# LED_Matrix.net
KiCad netlist of a schematic drawn in Altium Designer
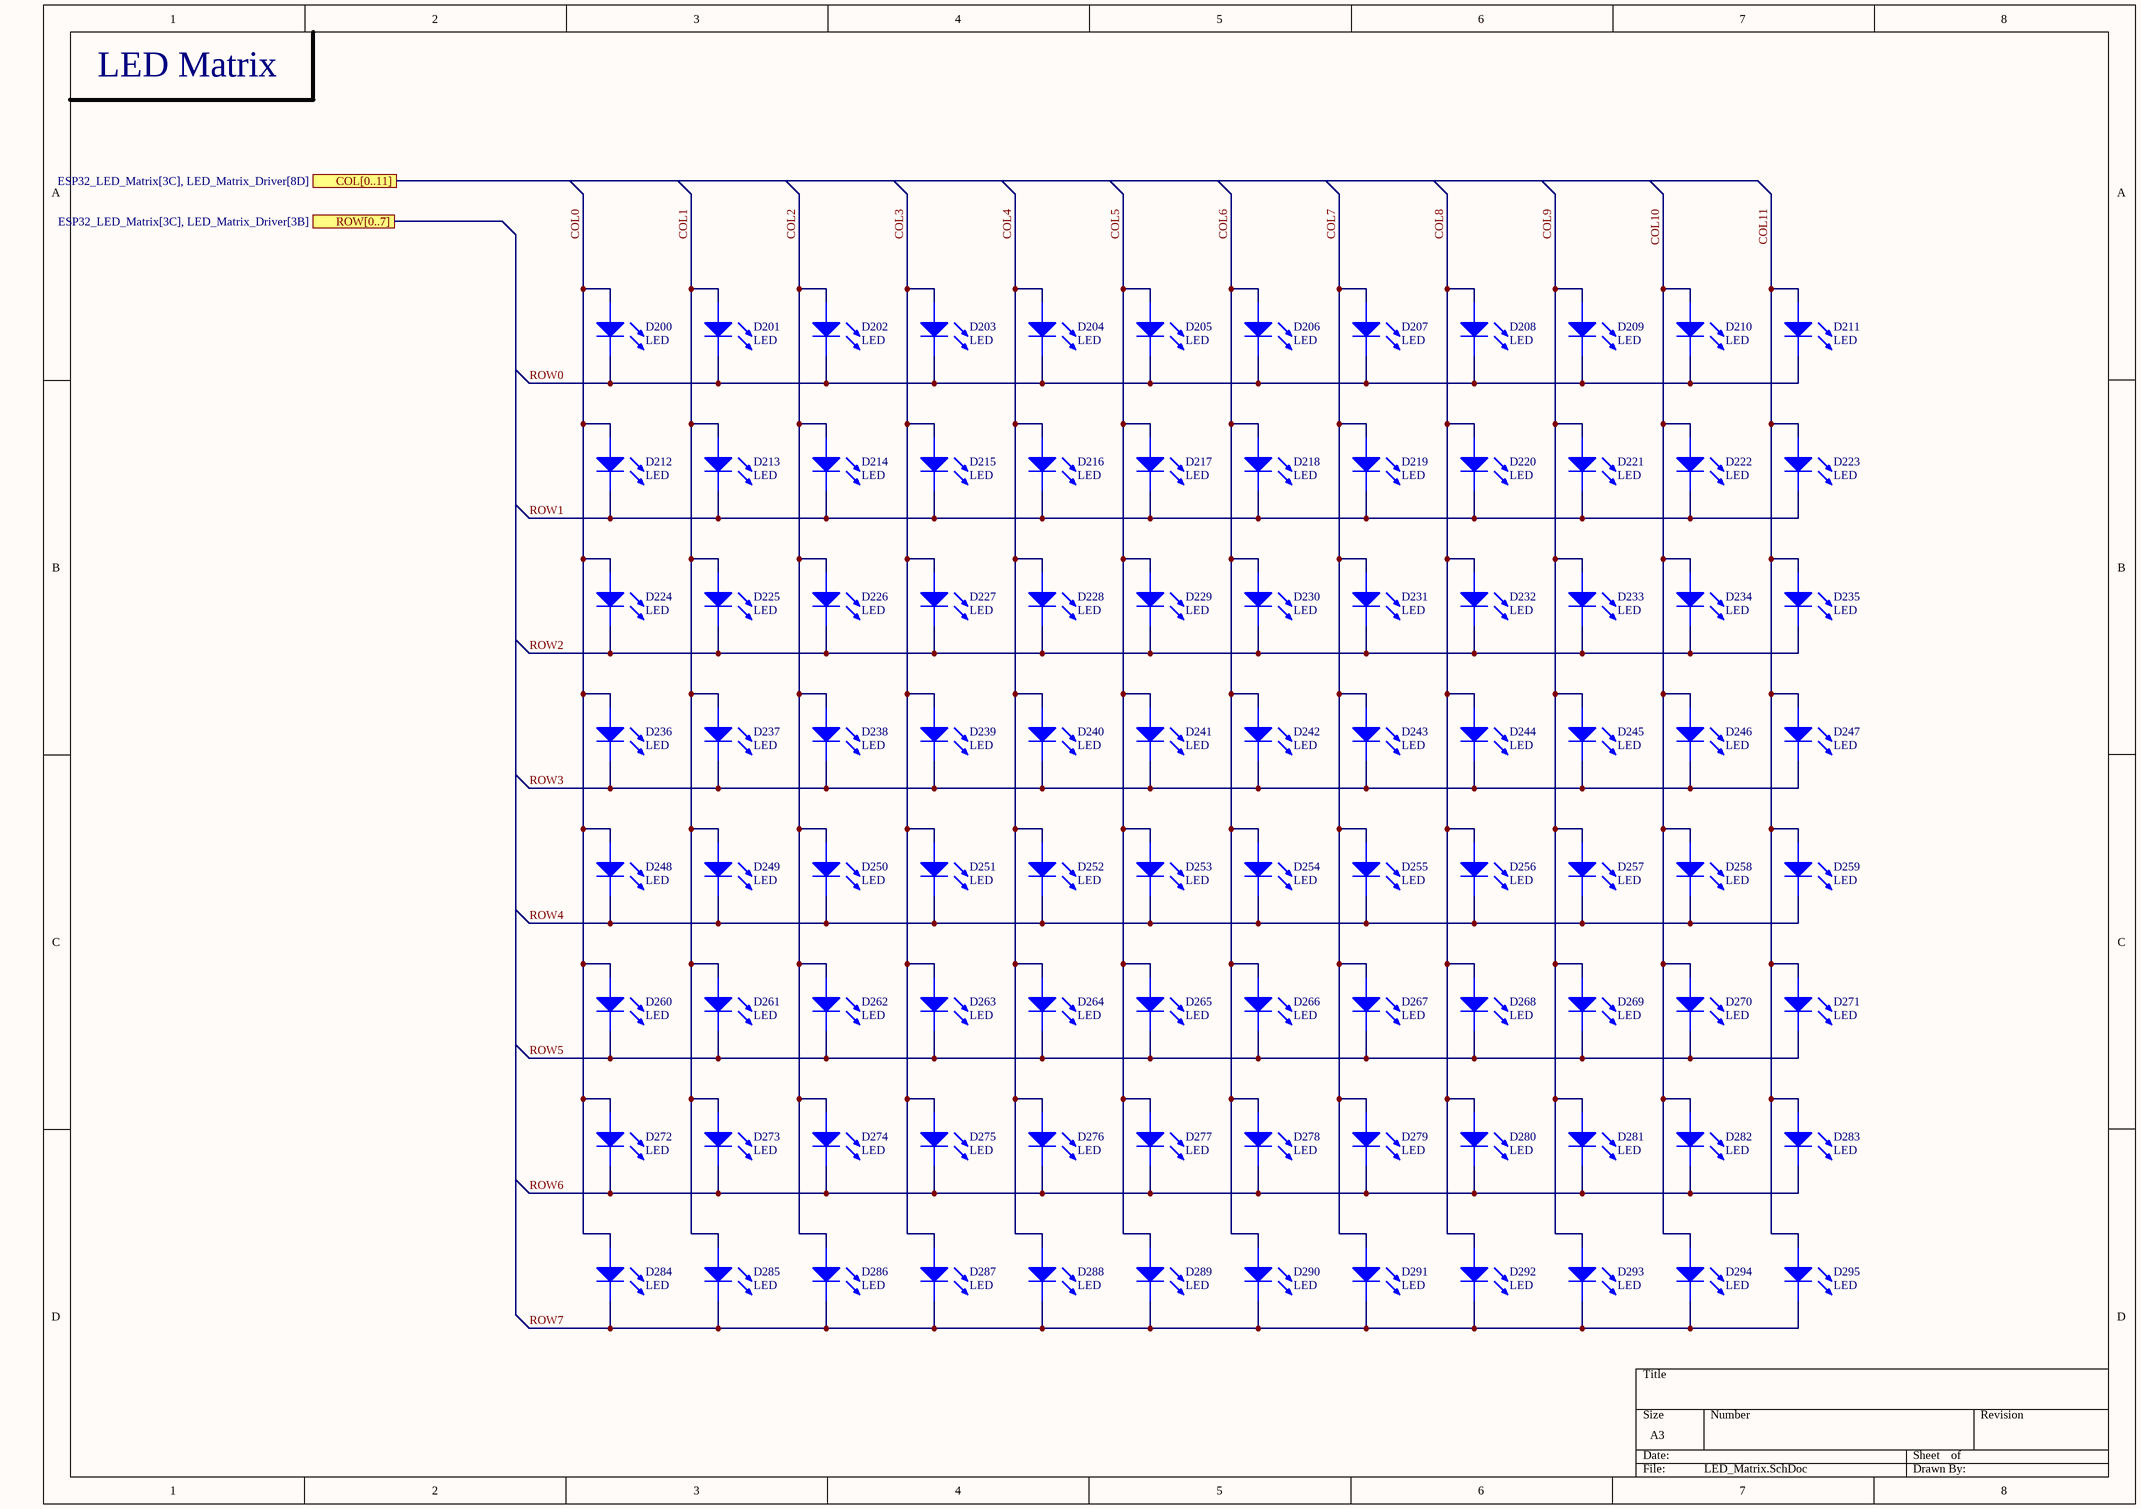
[diagram p0: LED_Matrix.SchDoc]

(export (version "E")
  (design (tool "Eeschema 10.0.6"))
  (components
    (comp (ref "D200")
      (value "LED")
      (footprint "IEEE_Workshop_Footprints:LEDM2012X80N")
      (description "General Purpose LED")
      (libsource (lib "TD") (part "LED"))
    )
    (comp (ref "D201")
      (value "LED")
      (footprint "IEEE_Workshop_Footprints:LEDM2012X80N")
      (description "General Purpose LED")
      (libsource (lib "TD") (part "LED"))
    )
    (comp (ref "D202")
      (value "LED")
      (footprint "IEEE_Workshop_Footprints:LEDM2012X80N")
      (description "General Purpose LED")
      (libsource (lib "TD") (part "LED"))
    )
    (comp (ref "D203")
      (value "LED")
      (footprint "IEEE_Workshop_Footprints:LEDM2012X80N")
      (description "General Purpose LED")
      (libsource (lib "TD") (part "LED"))
    )
    (comp (ref "D204")
      (value "LED")
      (footprint "IEEE_Workshop_Footprints:LEDM2012X80N")
      (description "General Purpose LED")
      (libsource (lib "TD") (part "LED"))
    )
    (comp (ref "D205")
      (value "LED")
      (footprint "IEEE_Workshop_Footprints:LEDM2012X80N")
      (description "General Purpose LED")
      (libsource (lib "TD") (part "LED"))
    )
    (comp (ref "D206")
      (value "LED")
      (footprint "IEEE_Workshop_Footprints:LEDM2012X80N")
      (description "General Purpose LED")
      (libsource (lib "TD") (part "LED"))
    )
    (comp (ref "D207")
      (value "LED")
      (footprint "IEEE_Workshop_Footprints:LEDM2012X80N")
      (description "General Purpose LED")
      (libsource (lib "TD") (part "LED"))
    )
    (comp (ref "D208")
      (value "LED")
      (footprint "IEEE_Workshop_Footprints:LEDM2012X80N")
      (description "General Purpose LED")
      (libsource (lib "TD") (part "LED"))
    )
    (comp (ref "D209")
      (value "LED")
      (footprint "IEEE_Workshop_Footprints:LEDM2012X80N")
      (description "General Purpose LED")
      (libsource (lib "TD") (part "LED"))
    )
    (comp (ref "D210")
      (value "LED")
      (footprint "IEEE_Workshop_Footprints:LEDM2012X80N")
      (description "General Purpose LED")
      (libsource (lib "TD") (part "LED"))
    )
    (comp (ref "D211")
      (value "LED")
      (footprint "IEEE_Workshop_Footprints:LEDM2012X80N")
      (description "General Purpose LED")
      (libsource (lib "TD") (part "LED"))
    )
    (comp (ref "D212")
      (value "LED")
      (footprint "IEEE_Workshop_Footprints:LEDM2012X80N")
      (description "General Purpose LED")
      (libsource (lib "TD") (part "LED"))
    )
    (comp (ref "D213")
      (value "LED")
      (footprint "IEEE_Workshop_Footprints:LEDM2012X80N")
      (description "General Purpose LED")
      (libsource (lib "TD") (part "LED"))
    )
    (comp (ref "D214")
      (value "LED")
      (footprint "IEEE_Workshop_Footprints:LEDM2012X80N")
      (description "General Purpose LED")
      (libsource (lib "TD") (part "LED"))
    )
    (comp (ref "D215")
      (value "LED")
      (footprint "IEEE_Workshop_Footprints:LEDM2012X80N")
      (description "General Purpose LED")
      (libsource (lib "TD") (part "LED"))
    )
    (comp (ref "D216")
      (value "LED")
      (footprint "IEEE_Workshop_Footprints:LEDM2012X80N")
      (description "General Purpose LED")
      (libsource (lib "TD") (part "LED"))
    )
    (comp (ref "D217")
      (value "LED")
      (footprint "IEEE_Workshop_Footprints:LEDM2012X80N")
      (description "General Purpose LED")
      (libsource (lib "TD") (part "LED"))
    )
    (comp (ref "D218")
      (value "LED")
      (footprint "IEEE_Workshop_Footprints:LEDM2012X80N")
      (description "General Purpose LED")
      (libsource (lib "TD") (part "LED"))
    )
    (comp (ref "D219")
      (value "LED")
      (footprint "IEEE_Workshop_Footprints:LEDM2012X80N")
      (description "General Purpose LED")
      (libsource (lib "TD") (part "LED"))
    )
    (comp (ref "D220")
      (value "LED")
      (footprint "IEEE_Workshop_Footprints:LEDM2012X80N")
      (description "General Purpose LED")
      (libsource (lib "TD") (part "LED"))
    )
    (comp (ref "D221")
      (value "LED")
      (footprint "IEEE_Workshop_Footprints:LEDM2012X80N")
      (description "General Purpose LED")
      (libsource (lib "TD") (part "LED"))
    )
    (comp (ref "D222")
      (value "LED")
      (footprint "IEEE_Workshop_Footprints:LEDM2012X80N")
      (description "General Purpose LED")
      (libsource (lib "TD") (part "LED"))
    )
    (comp (ref "D223")
      (value "LED")
      (footprint "IEEE_Workshop_Footprints:LEDM2012X80N")
      (description "General Purpose LED")
      (libsource (lib "TD") (part "LED"))
    )
    (comp (ref "D224")
      (value "LED")
      (footprint "IEEE_Workshop_Footprints:LEDM2012X80N")
      (description "General Purpose LED")
      (libsource (lib "TD") (part "LED"))
    )
    (comp (ref "D225")
      (value "LED")
      (footprint "IEEE_Workshop_Footprints:LEDM2012X80N")
      (description "General Purpose LED")
      (libsource (lib "TD") (part "LED"))
    )
    (comp (ref "D226")
      (value "LED")
      (footprint "IEEE_Workshop_Footprints:LEDM2012X80N")
      (description "General Purpose LED")
      (libsource (lib "TD") (part "LED"))
    )
    (comp (ref "D227")
      (value "LED")
      (footprint "IEEE_Workshop_Footprints:LEDM2012X80N")
      (description "General Purpose LED")
      (libsource (lib "TD") (part "LED"))
    )
    (comp (ref "D228")
      (value "LED")
      (footprint "IEEE_Workshop_Footprints:LEDM2012X80N")
      (description "General Purpose LED")
      (libsource (lib "TD") (part "LED"))
    )
    (comp (ref "D229")
      (value "LED")
      (footprint "IEEE_Workshop_Footprints:LEDM2012X80N")
      (description "General Purpose LED")
      (libsource (lib "TD") (part "LED"))
    )
    (comp (ref "D230")
      (value "LED")
      (footprint "IEEE_Workshop_Footprints:LEDM2012X80N")
      (description "General Purpose LED")
      (libsource (lib "TD") (part "LED"))
    )
    (comp (ref "D231")
      (value "LED")
      (footprint "IEEE_Workshop_Footprints:LEDM2012X80N")
      (description "General Purpose LED")
      (libsource (lib "TD") (part "LED"))
    )
    (comp (ref "D232")
      (value "LED")
      (footprint "IEEE_Workshop_Footprints:LEDM2012X80N")
      (description "General Purpose LED")
      (libsource (lib "TD") (part "LED"))
    )
    (comp (ref "D233")
      (value "LED")
      (footprint "IEEE_Workshop_Footprints:LEDM2012X80N")
      (description "General Purpose LED")
      (libsource (lib "TD") (part "LED"))
    )
    (comp (ref "D234")
      (value "LED")
      (footprint "IEEE_Workshop_Footprints:LEDM2012X80N")
      (description "General Purpose LED")
      (libsource (lib "TD") (part "LED"))
    )
    (comp (ref "D235")
      (value "LED")
      (footprint "IEEE_Workshop_Footprints:LEDM2012X80N")
      (description "General Purpose LED")
      (libsource (lib "TD") (part "LED"))
    )
    (comp (ref "D236")
      (value "LED")
      (footprint "IEEE_Workshop_Footprints:LEDM2012X80N")
      (description "General Purpose LED")
      (libsource (lib "TD") (part "LED"))
    )
    (comp (ref "D237")
      (value "LED")
      (footprint "IEEE_Workshop_Footprints:LEDM2012X80N")
      (description "General Purpose LED")
      (libsource (lib "TD") (part "LED"))
    )
    (comp (ref "D238")
      (value "LED")
      (footprint "IEEE_Workshop_Footprints:LEDM2012X80N")
      (description "General Purpose LED")
      (libsource (lib "TD") (part "LED"))
    )
    (comp (ref "D239")
      (value "LED")
      (footprint "IEEE_Workshop_Footprints:LEDM2012X80N")
      (description "General Purpose LED")
      (libsource (lib "TD") (part "LED"))
    )
    (comp (ref "D240")
      (value "LED")
      (footprint "IEEE_Workshop_Footprints:LEDM2012X80N")
      (description "General Purpose LED")
      (libsource (lib "TD") (part "LED"))
    )
    (comp (ref "D241")
      (value "LED")
      (footprint "IEEE_Workshop_Footprints:LEDM2012X80N")
      (description "General Purpose LED")
      (libsource (lib "TD") (part "LED"))
    )
    (comp (ref "D242")
      (value "LED")
      (footprint "IEEE_Workshop_Footprints:LEDM2012X80N")
      (description "General Purpose LED")
      (libsource (lib "TD") (part "LED"))
    )
    (comp (ref "D243")
      (value "LED")
      (footprint "IEEE_Workshop_Footprints:LEDM2012X80N")
      (description "General Purpose LED")
      (libsource (lib "TD") (part "LED"))
    )
    (comp (ref "D244")
      (value "LED")
      (footprint "IEEE_Workshop_Footprints:LEDM2012X80N")
      (description "General Purpose LED")
      (libsource (lib "TD") (part "LED"))
    )
    (comp (ref "D245")
      (value "LED")
      (footprint "IEEE_Workshop_Footprints:LEDM2012X80N")
      (description "General Purpose LED")
      (libsource (lib "TD") (part "LED"))
    )
    (comp (ref "D246")
      (value "LED")
      (footprint "IEEE_Workshop_Footprints:LEDM2012X80N")
      (description "General Purpose LED")
      (libsource (lib "TD") (part "LED"))
    )
    (comp (ref "D247")
      (value "LED")
      (footprint "IEEE_Workshop_Footprints:LEDM2012X80N")
      (description "General Purpose LED")
      (libsource (lib "TD") (part "LED"))
    )
    (comp (ref "D248")
      (value "LED")
      (footprint "IEEE_Workshop_Footprints:LEDM2012X80N")
      (description "General Purpose LED")
      (libsource (lib "TD") (part "LED"))
    )
    (comp (ref "D249")
      (value "LED")
      (footprint "IEEE_Workshop_Footprints:LEDM2012X80N")
      (description "General Purpose LED")
      (libsource (lib "TD") (part "LED"))
    )
    (comp (ref "D250")
      (value "LED")
      (footprint "IEEE_Workshop_Footprints:LEDM2012X80N")
      (description "General Purpose LED")
      (libsource (lib "TD") (part "LED"))
    )
    (comp (ref "D251")
      (value "LED")
      (footprint "IEEE_Workshop_Footprints:LEDM2012X80N")
      (description "General Purpose LED")
      (libsource (lib "TD") (part "LED"))
    )
    (comp (ref "D252")
      (value "LED")
      (footprint "IEEE_Workshop_Footprints:LEDM2012X80N")
      (description "General Purpose LED")
      (libsource (lib "TD") (part "LED"))
    )
    (comp (ref "D253")
      (value "LED")
      (footprint "IEEE_Workshop_Footprints:LEDM2012X80N")
      (description "General Purpose LED")
      (libsource (lib "TD") (part "LED"))
    )
    (comp (ref "D254")
      (value "LED")
      (footprint "IEEE_Workshop_Footprints:LEDM2012X80N")
      (description "General Purpose LED")
      (libsource (lib "TD") (part "LED"))
    )
    (comp (ref "D255")
      (value "LED")
      (footprint "IEEE_Workshop_Footprints:LEDM2012X80N")
      (description "General Purpose LED")
      (libsource (lib "TD") (part "LED"))
    )
    (comp (ref "D256")
      (value "LED")
      (footprint "IEEE_Workshop_Footprints:LEDM2012X80N")
      (description "General Purpose LED")
      (libsource (lib "TD") (part "LED"))
    )
    (comp (ref "D257")
      (value "LED")
      (footprint "IEEE_Workshop_Footprints:LEDM2012X80N")
      (description "General Purpose LED")
      (libsource (lib "TD") (part "LED"))
    )
    (comp (ref "D258")
      (value "LED")
      (footprint "IEEE_Workshop_Footprints:LEDM2012X80N")
      (description "General Purpose LED")
      (libsource (lib "TD") (part "LED"))
    )
    (comp (ref "D259")
      (value "LED")
      (footprint "IEEE_Workshop_Footprints:LEDM2012X80N")
      (description "General Purpose LED")
      (libsource (lib "TD") (part "LED"))
    )
    (comp (ref "D260")
      (value "LED")
      (footprint "IEEE_Workshop_Footprints:LEDM2012X80N")
      (description "General Purpose LED")
      (libsource (lib "TD") (part "LED"))
    )
    (comp (ref "D261")
      (value "LED")
      (footprint "IEEE_Workshop_Footprints:LEDM2012X80N")
      (description "General Purpose LED")
      (libsource (lib "TD") (part "LED"))
    )
    (comp (ref "D262")
      (value "LED")
      (footprint "IEEE_Workshop_Footprints:LEDM2012X80N")
      (description "General Purpose LED")
      (libsource (lib "TD") (part "LED"))
    )
    (comp (ref "D263")
      (value "LED")
      (footprint "IEEE_Workshop_Footprints:LEDM2012X80N")
      (description "General Purpose LED")
      (libsource (lib "TD") (part "LED"))
    )
    (comp (ref "D264")
      (value "LED")
      (footprint "IEEE_Workshop_Footprints:LEDM2012X80N")
      (description "General Purpose LED")
      (libsource (lib "TD") (part "LED"))
    )
    (comp (ref "D265")
      (value "LED")
      (footprint "IEEE_Workshop_Footprints:LEDM2012X80N")
      (description "General Purpose LED")
      (libsource (lib "TD") (part "LED"))
    )
    (comp (ref "D266")
      (value "LED")
      (footprint "IEEE_Workshop_Footprints:LEDM2012X80N")
      (description "General Purpose LED")
      (libsource (lib "TD") (part "LED"))
    )
    (comp (ref "D267")
      (value "LED")
      (footprint "IEEE_Workshop_Footprints:LEDM2012X80N")
      (description "General Purpose LED")
      (libsource (lib "TD") (part "LED"))
    )
    (comp (ref "D268")
      (value "LED")
      (footprint "IEEE_Workshop_Footprints:LEDM2012X80N")
      (description "General Purpose LED")
      (libsource (lib "TD") (part "LED"))
    )
    (comp (ref "D269")
      (value "LED")
      (footprint "IEEE_Workshop_Footprints:LEDM2012X80N")
      (description "General Purpose LED")
      (libsource (lib "TD") (part "LED"))
    )
    (comp (ref "D270")
      (value "LED")
      (footprint "IEEE_Workshop_Footprints:LEDM2012X80N")
      (description "General Purpose LED")
      (libsource (lib "TD") (part "LED"))
    )
    (comp (ref "D271")
      (value "LED")
      (footprint "IEEE_Workshop_Footprints:LEDM2012X80N")
      (description "General Purpose LED")
      (libsource (lib "TD") (part "LED"))
    )
    (comp (ref "D272")
      (value "LED")
      (footprint "IEEE_Workshop_Footprints:LEDM2012X80N")
      (description "General Purpose LED")
      (libsource (lib "TD") (part "LED"))
    )
    (comp (ref "D273")
      (value "LED")
      (footprint "IEEE_Workshop_Footprints:LEDM2012X80N")
      (description "General Purpose LED")
      (libsource (lib "TD") (part "LED"))
    )
    (comp (ref "D274")
      (value "LED")
      (footprint "IEEE_Workshop_Footprints:LEDM2012X80N")
      (description "General Purpose LED")
      (libsource (lib "TD") (part "LED"))
    )
    (comp (ref "D275")
      (value "LED")
      (footprint "IEEE_Workshop_Footprints:LEDM2012X80N")
      (description "General Purpose LED")
      (libsource (lib "TD") (part "LED"))
    )
    (comp (ref "D276")
      (value "LED")
      (footprint "IEEE_Workshop_Footprints:LEDM2012X80N")
      (description "General Purpose LED")
      (libsource (lib "TD") (part "LED"))
    )
    (comp (ref "D277")
      (value "LED")
      (footprint "IEEE_Workshop_Footprints:LEDM2012X80N")
      (description "General Purpose LED")
      (libsource (lib "TD") (part "LED"))
    )
    (comp (ref "D278")
      (value "LED")
      (footprint "IEEE_Workshop_Footprints:LEDM2012X80N")
      (description "General Purpose LED")
      (libsource (lib "TD") (part "LED"))
    )
    (comp (ref "D279")
      (value "LED")
      (footprint "IEEE_Workshop_Footprints:LEDM2012X80N")
      (description "General Purpose LED")
      (libsource (lib "TD") (part "LED"))
    )
    (comp (ref "D280")
      (value "LED")
      (footprint "IEEE_Workshop_Footprints:LEDM2012X80N")
      (description "General Purpose LED")
      (libsource (lib "TD") (part "LED"))
    )
    (comp (ref "D281")
      (value "LED")
      (footprint "IEEE_Workshop_Footprints:LEDM2012X80N")
      (description "General Purpose LED")
      (libsource (lib "TD") (part "LED"))
    )
    (comp (ref "D282")
      (value "LED")
      (footprint "IEEE_Workshop_Footprints:LEDM2012X80N")
      (description "General Purpose LED")
      (libsource (lib "TD") (part "LED"))
    )
    (comp (ref "D283")
      (value "LED")
      (footprint "IEEE_Workshop_Footprints:LEDM2012X80N")
      (description "General Purpose LED")
      (libsource (lib "TD") (part "LED"))
    )
    (comp (ref "D284")
      (value "LED")
      (footprint "IEEE_Workshop_Footprints:LEDM2012X80N")
      (description "General Purpose LED")
      (libsource (lib "TD") (part "LED"))
    )
    (comp (ref "D285")
      (value "LED")
      (footprint "IEEE_Workshop_Footprints:LEDM2012X80N")
      (description "General Purpose LED")
      (libsource (lib "TD") (part "LED"))
    )
    (comp (ref "D286")
      (value "LED")
      (footprint "IEEE_Workshop_Footprints:LEDM2012X80N")
      (description "General Purpose LED")
      (libsource (lib "TD") (part "LED"))
    )
    (comp (ref "D287")
      (value "LED")
      (footprint "IEEE_Workshop_Footprints:LEDM2012X80N")
      (description "General Purpose LED")
      (libsource (lib "TD") (part "LED"))
    )
    (comp (ref "D288")
      (value "LED")
      (footprint "IEEE_Workshop_Footprints:LEDM2012X80N")
      (description "General Purpose LED")
      (libsource (lib "TD") (part "LED"))
    )
    (comp (ref "D289")
      (value "LED")
      (footprint "IEEE_Workshop_Footprints:LEDM2012X80N")
      (description "General Purpose LED")
      (libsource (lib "TD") (part "LED"))
    )
    (comp (ref "D290")
      (value "LED")
      (footprint "IEEE_Workshop_Footprints:LEDM2012X80N")
      (description "General Purpose LED")
      (libsource (lib "TD") (part "LED"))
    )
    (comp (ref "D291")
      (value "LED")
      (footprint "IEEE_Workshop_Footprints:LEDM2012X80N")
      (description "General Purpose LED")
      (libsource (lib "TD") (part "LED"))
    )
    (comp (ref "D292")
      (value "LED")
      (footprint "IEEE_Workshop_Footprints:LEDM2012X80N")
      (description "General Purpose LED")
      (libsource (lib "TD") (part "LED"))
    )
    (comp (ref "D293")
      (value "LED")
      (footprint "IEEE_Workshop_Footprints:LEDM2012X80N")
      (description "General Purpose LED")
      (libsource (lib "TD") (part "LED"))
    )
    (comp (ref "D294")
      (value "LED")
      (footprint "IEEE_Workshop_Footprints:LEDM2012X80N")
      (description "General Purpose LED")
      (libsource (lib "TD") (part "LED"))
    )
    (comp (ref "D295")
      (value "LED")
      (footprint "IEEE_Workshop_Footprints:LEDM2012X80N")
      (description "General Purpose LED")
      (libsource (lib "TD") (part "LED"))
    )
  )
  (nets
    (net (code "1") (name "/COL0") (class "Default")
      (node (ref "D200") (pin "2") (pinfunction "A_2") (pintype "passive"))
      (node (ref "D212") (pin "2") (pinfunction "A_2") (pintype "passive"))
      (node (ref "D224") (pin "2") (pinfunction "A_2") (pintype "passive"))
      (node (ref "D236") (pin "2") (pinfunction "A_2") (pintype "passive"))
      (node (ref "D248") (pin "2") (pinfunction "A_2") (pintype "passive"))
      (node (ref "D260") (pin "2") (pinfunction "A_2") (pintype "passive"))
      (node (ref "D272") (pin "2") (pinfunction "A_2") (pintype "passive"))
      (node (ref "D284") (pin "2") (pinfunction "A_2") (pintype "passive"))
    )
    (net (code "2") (name "/COL1") (class "Default")
      (node (ref "D201") (pin "2") (pinfunction "A_2") (pintype "passive"))
      (node (ref "D213") (pin "2") (pinfunction "A_2") (pintype "passive"))
      (node (ref "D225") (pin "2") (pinfunction "A_2") (pintype "passive"))
      (node (ref "D237") (pin "2") (pinfunction "A_2") (pintype "passive"))
      (node (ref "D249") (pin "2") (pinfunction "A_2") (pintype "passive"))
      (node (ref "D261") (pin "2") (pinfunction "A_2") (pintype "passive"))
      (node (ref "D273") (pin "2") (pinfunction "A_2") (pintype "passive"))
      (node (ref "D285") (pin "2") (pinfunction "A_2") (pintype "passive"))
    )
    (net (code "3") (name "/COL2") (class "Default")
      (node (ref "D202") (pin "2") (pinfunction "A_2") (pintype "passive"))
      (node (ref "D214") (pin "2") (pinfunction "A_2") (pintype "passive"))
      (node (ref "D226") (pin "2") (pinfunction "A_2") (pintype "passive"))
      (node (ref "D238") (pin "2") (pinfunction "A_2") (pintype "passive"))
      (node (ref "D250") (pin "2") (pinfunction "A_2") (pintype "passive"))
      (node (ref "D262") (pin "2") (pinfunction "A_2") (pintype "passive"))
      (node (ref "D274") (pin "2") (pinfunction "A_2") (pintype "passive"))
      (node (ref "D286") (pin "2") (pinfunction "A_2") (pintype "passive"))
    )
    (net (code "4") (name "/COL3") (class "Default")
      (node (ref "D203") (pin "2") (pinfunction "A_2") (pintype "passive"))
      (node (ref "D215") (pin "2") (pinfunction "A_2") (pintype "passive"))
      (node (ref "D227") (pin "2") (pinfunction "A_2") (pintype "passive"))
      (node (ref "D239") (pin "2") (pinfunction "A_2") (pintype "passive"))
      (node (ref "D251") (pin "2") (pinfunction "A_2") (pintype "passive"))
      (node (ref "D263") (pin "2") (pinfunction "A_2") (pintype "passive"))
      (node (ref "D275") (pin "2") (pinfunction "A_2") (pintype "passive"))
      (node (ref "D287") (pin "2") (pinfunction "A_2") (pintype "passive"))
    )
    (net (code "5") (name "/COL4") (class "Default")
      (node (ref "D204") (pin "2") (pinfunction "A_2") (pintype "passive"))
      (node (ref "D216") (pin "2") (pinfunction "A_2") (pintype "passive"))
      (node (ref "D228") (pin "2") (pinfunction "A_2") (pintype "passive"))
      (node (ref "D240") (pin "2") (pinfunction "A_2") (pintype "passive"))
      (node (ref "D252") (pin "2") (pinfunction "A_2") (pintype "passive"))
      (node (ref "D264") (pin "2") (pinfunction "A_2") (pintype "passive"))
      (node (ref "D276") (pin "2") (pinfunction "A_2") (pintype "passive"))
      (node (ref "D288") (pin "2") (pinfunction "A_2") (pintype "passive"))
    )
    (net (code "6") (name "/COL5") (class "Default")
      (node (ref "D205") (pin "2") (pinfunction "A_2") (pintype "passive"))
      (node (ref "D217") (pin "2") (pinfunction "A_2") (pintype "passive"))
      (node (ref "D229") (pin "2") (pinfunction "A_2") (pintype "passive"))
      (node (ref "D241") (pin "2") (pinfunction "A_2") (pintype "passive"))
      (node (ref "D253") (pin "2") (pinfunction "A_2") (pintype "passive"))
      (node (ref "D265") (pin "2") (pinfunction "A_2") (pintype "passive"))
      (node (ref "D277") (pin "2") (pinfunction "A_2") (pintype "passive"))
      (node (ref "D289") (pin "2") (pinfunction "A_2") (pintype "passive"))
    )
    (net (code "7") (name "/COL6") (class "Default")
      (node (ref "D206") (pin "2") (pinfunction "A_2") (pintype "passive"))
      (node (ref "D218") (pin "2") (pinfunction "A_2") (pintype "passive"))
      (node (ref "D230") (pin "2") (pinfunction "A_2") (pintype "passive"))
      (node (ref "D242") (pin "2") (pinfunction "A_2") (pintype "passive"))
      (node (ref "D254") (pin "2") (pinfunction "A_2") (pintype "passive"))
      (node (ref "D266") (pin "2") (pinfunction "A_2") (pintype "passive"))
      (node (ref "D278") (pin "2") (pinfunction "A_2") (pintype "passive"))
      (node (ref "D290") (pin "2") (pinfunction "A_2") (pintype "passive"))
    )
    (net (code "8") (name "/COL7") (class "Default")
      (node (ref "D207") (pin "2") (pinfunction "A_2") (pintype "passive"))
      (node (ref "D219") (pin "2") (pinfunction "A_2") (pintype "passive"))
      (node (ref "D231") (pin "2") (pinfunction "A_2") (pintype "passive"))
      (node (ref "D243") (pin "2") (pinfunction "A_2") (pintype "passive"))
      (node (ref "D255") (pin "2") (pinfunction "A_2") (pintype "passive"))
      (node (ref "D267") (pin "2") (pinfunction "A_2") (pintype "passive"))
      (node (ref "D279") (pin "2") (pinfunction "A_2") (pintype "passive"))
      (node (ref "D291") (pin "2") (pinfunction "A_2") (pintype "passive"))
    )
    (net (code "9") (name "/COL8") (class "Default")
      (node (ref "D208") (pin "2") (pinfunction "A_2") (pintype "passive"))
      (node (ref "D220") (pin "2") (pinfunction "A_2") (pintype "passive"))
      (node (ref "D232") (pin "2") (pinfunction "A_2") (pintype "passive"))
      (node (ref "D244") (pin "2") (pinfunction "A_2") (pintype "passive"))
      (node (ref "D256") (pin "2") (pinfunction "A_2") (pintype "passive"))
      (node (ref "D268") (pin "2") (pinfunction "A_2") (pintype "passive"))
      (node (ref "D280") (pin "2") (pinfunction "A_2") (pintype "passive"))
      (node (ref "D292") (pin "2") (pinfunction "A_2") (pintype "passive"))
    )
    (net (code "10") (name "/COL9") (class "Default")
      (node (ref "D209") (pin "2") (pinfunction "A_2") (pintype "passive"))
      (node (ref "D221") (pin "2") (pinfunction "A_2") (pintype "passive"))
      (node (ref "D233") (pin "2") (pinfunction "A_2") (pintype "passive"))
      (node (ref "D245") (pin "2") (pinfunction "A_2") (pintype "passive"))
      (node (ref "D257") (pin "2") (pinfunction "A_2") (pintype "passive"))
      (node (ref "D269") (pin "2") (pinfunction "A_2") (pintype "passive"))
      (node (ref "D281") (pin "2") (pinfunction "A_2") (pintype "passive"))
      (node (ref "D293") (pin "2") (pinfunction "A_2") (pintype "passive"))
    )
    (net (code "11") (name "/COL10") (class "Default")
      (node (ref "D210") (pin "2") (pinfunction "A_2") (pintype "passive"))
      (node (ref "D222") (pin "2") (pinfunction "A_2") (pintype "passive"))
      (node (ref "D234") (pin "2") (pinfunction "A_2") (pintype "passive"))
      (node (ref "D246") (pin "2") (pinfunction "A_2") (pintype "passive"))
      (node (ref "D258") (pin "2") (pinfunction "A_2") (pintype "passive"))
      (node (ref "D270") (pin "2") (pinfunction "A_2") (pintype "passive"))
      (node (ref "D282") (pin "2") (pinfunction "A_2") (pintype "passive"))
      (node (ref "D294") (pin "2") (pinfunction "A_2") (pintype "passive"))
    )
    (net (code "12") (name "/COL11") (class "Default")
      (node (ref "D211") (pin "2") (pinfunction "A_2") (pintype "passive"))
      (node (ref "D223") (pin "2") (pinfunction "A_2") (pintype "passive"))
      (node (ref "D235") (pin "2") (pinfunction "A_2") (pintype "passive"))
      (node (ref "D247") (pin "2") (pinfunction "A_2") (pintype "passive"))
      (node (ref "D259") (pin "2") (pinfunction "A_2") (pintype "passive"))
      (node (ref "D271") (pin "2") (pinfunction "A_2") (pintype "passive"))
      (node (ref "D283") (pin "2") (pinfunction "A_2") (pintype "passive"))
      (node (ref "D295") (pin "2") (pinfunction "A_2") (pintype "passive"))
    )
    (net (code "14") (name "/ROW0") (class "Default")
      (node (ref "D200") (pin "1") (pinfunction "K_1") (pintype "passive"))
      (node (ref "D201") (pin "1") (pinfunction "K_1") (pintype "passive"))
      (node (ref "D202") (pin "1") (pinfunction "K_1") (pintype "passive"))
      (node (ref "D203") (pin "1") (pinfunction "K_1") (pintype "passive"))
      (node (ref "D204") (pin "1") (pinfunction "K_1") (pintype "passive"))
      (node (ref "D205") (pin "1") (pinfunction "K_1") (pintype "passive"))
      (node (ref "D206") (pin "1") (pinfunction "K_1") (pintype "passive"))
      (node (ref "D207") (pin "1") (pinfunction "K_1") (pintype "passive"))
      (node (ref "D208") (pin "1") (pinfunction "K_1") (pintype "passive"))
      (node (ref "D209") (pin "1") (pinfunction "K_1") (pintype "passive"))
      (node (ref "D210") (pin "1") (pinfunction "K_1") (pintype "passive"))
      (node (ref "D211") (pin "1") (pinfunction "K_1") (pintype "passive"))
    )
    (net (code "15") (name "/ROW1") (class "Default")
      (node (ref "D212") (pin "1") (pinfunction "K_1") (pintype "passive"))
      (node (ref "D213") (pin "1") (pinfunction "K_1") (pintype "passive"))
      (node (ref "D214") (pin "1") (pinfunction "K_1") (pintype "passive"))
      (node (ref "D215") (pin "1") (pinfunction "K_1") (pintype "passive"))
      (node (ref "D216") (pin "1") (pinfunction "K_1") (pintype "passive"))
      (node (ref "D217") (pin "1") (pinfunction "K_1") (pintype "passive"))
      (node (ref "D218") (pin "1") (pinfunction "K_1") (pintype "passive"))
      (node (ref "D219") (pin "1") (pinfunction "K_1") (pintype "passive"))
      (node (ref "D220") (pin "1") (pinfunction "K_1") (pintype "passive"))
      (node (ref "D221") (pin "1") (pinfunction "K_1") (pintype "passive"))
      (node (ref "D222") (pin "1") (pinfunction "K_1") (pintype "passive"))
      (node (ref "D223") (pin "1") (pinfunction "K_1") (pintype "passive"))
    )
    (net (code "16") (name "/ROW2") (class "Default")
      (node (ref "D224") (pin "1") (pinfunction "K_1") (pintype "passive"))
      (node (ref "D225") (pin "1") (pinfunction "K_1") (pintype "passive"))
      (node (ref "D226") (pin "1") (pinfunction "K_1") (pintype "passive"))
      (node (ref "D227") (pin "1") (pinfunction "K_1") (pintype "passive"))
      (node (ref "D228") (pin "1") (pinfunction "K_1") (pintype "passive"))
      (node (ref "D229") (pin "1") (pinfunction "K_1") (pintype "passive"))
      (node (ref "D230") (pin "1") (pinfunction "K_1") (pintype "passive"))
      (node (ref "D231") (pin "1") (pinfunction "K_1") (pintype "passive"))
      (node (ref "D232") (pin "1") (pinfunction "K_1") (pintype "passive"))
      (node (ref "D233") (pin "1") (pinfunction "K_1") (pintype "passive"))
      (node (ref "D234") (pin "1") (pinfunction "K_1") (pintype "passive"))
      (node (ref "D235") (pin "1") (pinfunction "K_1") (pintype "passive"))
    )
    (net (code "17") (name "/ROW3") (class "Default")
      (node (ref "D236") (pin "1") (pinfunction "K_1") (pintype "passive"))
      (node (ref "D237") (pin "1") (pinfunction "K_1") (pintype "passive"))
      (node (ref "D238") (pin "1") (pinfunction "K_1") (pintype "passive"))
      (node (ref "D239") (pin "1") (pinfunction "K_1") (pintype "passive"))
      (node (ref "D240") (pin "1") (pinfunction "K_1") (pintype "passive"))
      (node (ref "D241") (pin "1") (pinfunction "K_1") (pintype "passive"))
      (node (ref "D242") (pin "1") (pinfunction "K_1") (pintype "passive"))
      (node (ref "D243") (pin "1") (pinfunction "K_1") (pintype "passive"))
      (node (ref "D244") (pin "1") (pinfunction "K_1") (pintype "passive"))
      (node (ref "D245") (pin "1") (pinfunction "K_1") (pintype "passive"))
      (node (ref "D246") (pin "1") (pinfunction "K_1") (pintype "passive"))
      (node (ref "D247") (pin "1") (pinfunction "K_1") (pintype "passive"))
    )
    (net (code "18") (name "/ROW4") (class "Default")
      (node (ref "D248") (pin "1") (pinfunction "K_1") (pintype "passive"))
      (node (ref "D249") (pin "1") (pinfunction "K_1") (pintype "passive"))
      (node (ref "D250") (pin "1") (pinfunction "K_1") (pintype "passive"))
      (node (ref "D251") (pin "1") (pinfunction "K_1") (pintype "passive"))
      (node (ref "D252") (pin "1") (pinfunction "K_1") (pintype "passive"))
      (node (ref "D253") (pin "1") (pinfunction "K_1") (pintype "passive"))
      (node (ref "D254") (pin "1") (pinfunction "K_1") (pintype "passive"))
      (node (ref "D255") (pin "1") (pinfunction "K_1") (pintype "passive"))
      (node (ref "D256") (pin "1") (pinfunction "K_1") (pintype "passive"))
      (node (ref "D257") (pin "1") (pinfunction "K_1") (pintype "passive"))
      (node (ref "D258") (pin "1") (pinfunction "K_1") (pintype "passive"))
      (node (ref "D259") (pin "1") (pinfunction "K_1") (pintype "passive"))
    )
    (net (code "19") (name "/ROW5") (class "Default")
      (node (ref "D260") (pin "1") (pinfunction "K_1") (pintype "passive"))
      (node (ref "D261") (pin "1") (pinfunction "K_1") (pintype "passive"))
      (node (ref "D262") (pin "1") (pinfunction "K_1") (pintype "passive"))
      (node (ref "D263") (pin "1") (pinfunction "K_1") (pintype "passive"))
      (node (ref "D264") (pin "1") (pinfunction "K_1") (pintype "passive"))
      (node (ref "D265") (pin "1") (pinfunction "K_1") (pintype "passive"))
      (node (ref "D266") (pin "1") (pinfunction "K_1") (pintype "passive"))
      (node (ref "D267") (pin "1") (pinfunction "K_1") (pintype "passive"))
      (node (ref "D268") (pin "1") (pinfunction "K_1") (pintype "passive"))
      (node (ref "D269") (pin "1") (pinfunction "K_1") (pintype "passive"))
      (node (ref "D270") (pin "1") (pinfunction "K_1") (pintype "passive"))
      (node (ref "D271") (pin "1") (pinfunction "K_1") (pintype "passive"))
    )
    (net (code "20") (name "/ROW6") (class "Default")
      (node (ref "D272") (pin "1") (pinfunction "K_1") (pintype "passive"))
      (node (ref "D273") (pin "1") (pinfunction "K_1") (pintype "passive"))
      (node (ref "D274") (pin "1") (pinfunction "K_1") (pintype "passive"))
      (node (ref "D275") (pin "1") (pinfunction "K_1") (pintype "passive"))
      (node (ref "D276") (pin "1") (pinfunction "K_1") (pintype "passive"))
      (node (ref "D277") (pin "1") (pinfunction "K_1") (pintype "passive"))
      (node (ref "D278") (pin "1") (pinfunction "K_1") (pintype "passive"))
      (node (ref "D279") (pin "1") (pinfunction "K_1") (pintype "passive"))
      (node (ref "D280") (pin "1") (pinfunction "K_1") (pintype "passive"))
      (node (ref "D281") (pin "1") (pinfunction "K_1") (pintype "passive"))
      (node (ref "D282") (pin "1") (pinfunction "K_1") (pintype "passive"))
      (node (ref "D283") (pin "1") (pinfunction "K_1") (pintype "passive"))
    )
    (net (code "21") (name "/ROW7") (class "Default")
      (node (ref "D284") (pin "1") (pinfunction "K_1") (pintype "passive"))
      (node (ref "D285") (pin "1") (pinfunction "K_1") (pintype "passive"))
      (node (ref "D286") (pin "1") (pinfunction "K_1") (pintype "passive"))
      (node (ref "D287") (pin "1") (pinfunction "K_1") (pintype "passive"))
      (node (ref "D288") (pin "1") (pinfunction "K_1") (pintype "passive"))
      (node (ref "D289") (pin "1") (pinfunction "K_1") (pintype "passive"))
      (node (ref "D290") (pin "1") (pinfunction "K_1") (pintype "passive"))
      (node (ref "D291") (pin "1") (pinfunction "K_1") (pintype "passive"))
      (node (ref "D292") (pin "1") (pinfunction "K_1") (pintype "passive"))
      (node (ref "D293") (pin "1") (pinfunction "K_1") (pintype "passive"))
      (node (ref "D294") (pin "1") (pinfunction "K_1") (pintype "passive"))
      (node (ref "D295") (pin "1") (pinfunction "K_1") (pintype "passive"))
    )
  )
)
